# conn_board_v0_1.net
KiCad netlist of a schematic drawn in EAGLE
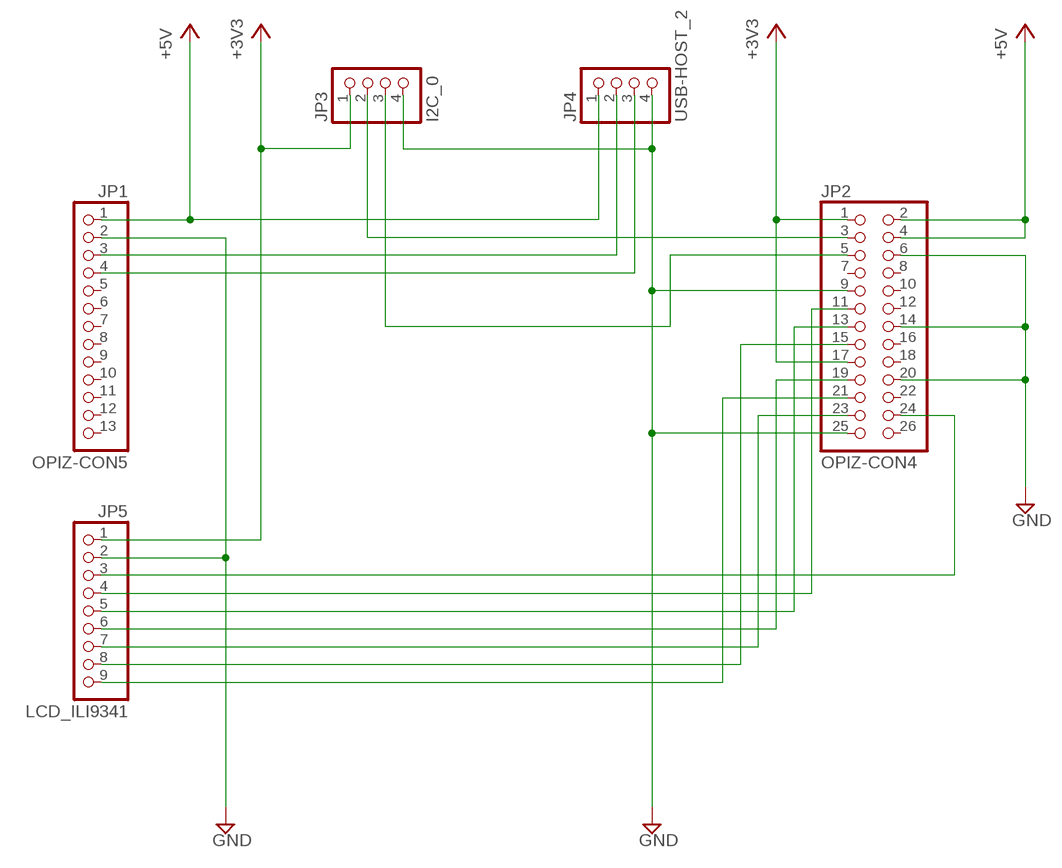
[diagram p0: schematic, sheet 1]

(export (version "E")
  (design (tool "Eeschema 10.0.6"))
  (components
    (comp (ref "JP1")
      (value "OPIZ-CON5")
      (footprint "eagle-import:1X13")
      (libsource (lib "eagle-import") (part "PINHD-1X13"))
    )
    (comp (ref "JP2")
      (value "OPIZ-CON4")
      (footprint "eagle-import:2X13")
      (libsource (lib "eagle-import") (part "PINHD-2X13"))
    )
    (comp (ref "JP3")
      (value "I2C_0")
      (footprint "eagle-import:1X04")
      (libsource (lib "eagle-import") (part "PINHD-1X4"))
    )
    (comp (ref "JP4")
      (value "USB-HOST_2")
      (footprint "eagle-import:1X04")
      (libsource (lib "eagle-import") (part "PINHD-1X4"))
    )
    (comp (ref "JP5")
      (value "LCD_ILI9341")
      (footprint "eagle-import:1X09")
      (libsource (lib "eagle-import") (part "PINHD-1X9"))
    )
  )
  (nets
    (net (code "1") (name "+3V3") (class "Default")
      (node (ref "JP2") (pin "1") (pinfunction "1_1") (pintype "passive"))
      (node (ref "JP2") (pin "17") (pinfunction "17_17") (pintype "passive"))
      (node (ref "JP3") (pin "1") (pinfunction "1_1") (pintype "passive"))
      (node (ref "JP5") (pin "1") (pinfunction "1_1") (pintype "passive"))
    )
    (net (code "2") (name "+5V") (class "Default")
      (node (ref "JP1") (pin "1") (pinfunction "1_1") (pintype "passive"))
      (node (ref "JP2") (pin "2") (pinfunction "2_2") (pintype "passive"))
      (node (ref "JP2") (pin "4") (pinfunction "4_4") (pintype "passive"))
      (node (ref "JP4") (pin "1") (pinfunction "1_1") (pintype "passive"))
    )
    (net (code "3") (name "GND") (class "Default")
      (node (ref "JP1") (pin "2") (pinfunction "2_2") (pintype "passive"))
      (node (ref "JP2") (pin "14") (pinfunction "14_14") (pintype "passive"))
      (node (ref "JP2") (pin "20") (pinfunction "20_20") (pintype "passive"))
      (node (ref "JP2") (pin "25") (pinfunction "25_25") (pintype "passive"))
      (node (ref "JP2") (pin "6") (pinfunction "6_6") (pintype "passive"))
      (node (ref "JP2") (pin "9") (pinfunction "9_9") (pintype "passive"))
      (node (ref "JP3") (pin "4") (pinfunction "4_4") (pintype "passive"))
      (node (ref "JP4") (pin "4") (pinfunction "4_4") (pintype "passive"))
      (node (ref "JP5") (pin "2") (pinfunction "2_2") (pintype "passive"))
    )
    (net (code "4") (name "Net-(JP1-Pad3)") (class "Default")
      (node (ref "JP1") (pin "3") (pinfunction "3_3") (pintype "passive"))
      (node (ref "JP4") (pin "2") (pinfunction "2_2") (pintype "passive"))
    )
    (net (code "5") (name "Net-(JP1-Pad4)") (class "Default")
      (node (ref "JP1") (pin "4") (pinfunction "4_4") (pintype "passive"))
      (node (ref "JP4") (pin "3") (pinfunction "3_3") (pintype "passive"))
    )
    (net (code "6") (name "Net-(JP2-Pad3)") (class "Default")
      (node (ref "JP2") (pin "3") (pinfunction "3_3") (pintype "passive"))
      (node (ref "JP3") (pin "2") (pinfunction "2_2") (pintype "passive"))
    )
    (net (code "7") (name "Net-(JP2-Pad5)") (class "Default")
      (node (ref "JP2") (pin "5") (pinfunction "5_5") (pintype "passive"))
      (node (ref "JP3") (pin "3") (pinfunction "3_3") (pintype "passive"))
    )
    (net (code "8") (name "Net-(JP2-Pad11)") (class "Default")
      (node (ref "JP2") (pin "11") (pinfunction "11_11") (pintype "passive"))
      (node (ref "JP5") (pin "4") (pinfunction "4_4") (pintype "passive"))
    )
    (net (code "9") (name "Net-(JP2-Pad13)") (class "Default")
      (node (ref "JP2") (pin "13") (pinfunction "13_13") (pintype "passive"))
      (node (ref "JP5") (pin "5") (pinfunction "5_5") (pintype "passive"))
    )
    (net (code "10") (name "Net-(JP2-Pad15)") (class "Default")
      (node (ref "JP2") (pin "15") (pinfunction "15_15") (pintype "passive"))
      (node (ref "JP5") (pin "8") (pinfunction "8_8") (pintype "passive"))
    )
    (net (code "11") (name "Net-(JP2-Pad19)") (class "Default")
      (node (ref "JP2") (pin "19") (pinfunction "19_19") (pintype "passive"))
      (node (ref "JP5") (pin "6") (pinfunction "6_6") (pintype "passive"))
    )
    (net (code "12") (name "Net-(JP2-Pad21)") (class "Default")
      (node (ref "JP2") (pin "21") (pinfunction "21_21") (pintype "passive"))
      (node (ref "JP5") (pin "9") (pinfunction "9_9") (pintype "passive"))
    )
    (net (code "13") (name "Net-(JP2-Pad23)") (class "Default")
      (node (ref "JP2") (pin "23") (pinfunction "23_23") (pintype "passive"))
      (node (ref "JP5") (pin "7") (pinfunction "7_7") (pintype "passive"))
    )
    (net (code "14") (name "Net-(JP2-Pad24)") (class "Default")
      (node (ref "JP2") (pin "24") (pinfunction "24_24") (pintype "passive"))
      (node (ref "JP5") (pin "3") (pinfunction "3_3") (pintype "passive"))
    )
    (net (code "15") (name "unconnected-(JP1-Pad5)") (class "Default")
      (node (ref "JP1") (pin "5") (pinfunction "5_5") (pintype "passive"))
    )
    (net (code "16") (name "unconnected-(JP1-Pad6)") (class "Default")
      (node (ref "JP1") (pin "6") (pinfunction "6_6") (pintype "passive"))
    )
    (net (code "17") (name "unconnected-(JP1-Pad7)") (class "Default")
      (node (ref "JP1") (pin "7") (pinfunction "7_7") (pintype "passive"))
    )
    (net (code "18") (name "unconnected-(JP1-Pad8)") (class "Default")
      (node (ref "JP1") (pin "8") (pinfunction "8_8") (pintype "passive"))
    )
    (net (code "19") (name "unconnected-(JP1-Pad9)") (class "Default")
      (node (ref "JP1") (pin "9") (pinfunction "9_9") (pintype "passive"))
    )
    (net (code "20") (name "unconnected-(JP1-Pad10)") (class "Default")
      (node (ref "JP1") (pin "10") (pinfunction "10_10") (pintype "passive"))
    )
    (net (code "21") (name "unconnected-(JP1-Pad11)") (class "Default")
      (node (ref "JP1") (pin "11") (pinfunction "11_11") (pintype "passive"))
    )
    (net (code "22") (name "unconnected-(JP1-Pad12)") (class "Default")
      (node (ref "JP1") (pin "12") (pinfunction "12_12") (pintype "passive"))
    )
    (net (code "23") (name "unconnected-(JP1-Pad13)") (class "Default")
      (node (ref "JP1") (pin "13") (pinfunction "13_13") (pintype "passive"))
    )
    (net (code "24") (name "unconnected-(JP2-Pad7)") (class "Default")
      (node (ref "JP2") (pin "7") (pinfunction "7_7") (pintype "passive"))
    )
    (net (code "25") (name "unconnected-(JP2-Pad8)") (class "Default")
      (node (ref "JP2") (pin "8") (pinfunction "8_8") (pintype "passive"))
    )
    (net (code "26") (name "unconnected-(JP2-Pad10)") (class "Default")
      (node (ref "JP2") (pin "10") (pinfunction "10_10") (pintype "passive"))
    )
    (net (code "27") (name "unconnected-(JP2-Pad12)") (class "Default")
      (node (ref "JP2") (pin "12") (pinfunction "12_12") (pintype "passive"))
    )
    (net (code "28") (name "unconnected-(JP2-Pad16)") (class "Default")
      (node (ref "JP2") (pin "16") (pinfunction "16_16") (pintype "passive"))
    )
    (net (code "29") (name "unconnected-(JP2-Pad18)") (class "Default")
      (node (ref "JP2") (pin "18") (pinfunction "18_18") (pintype "passive"))
    )
    (net (code "30") (name "unconnected-(JP2-Pad22)") (class "Default")
      (node (ref "JP2") (pin "22") (pinfunction "22_22") (pintype "passive"))
    )
    (net (code "31") (name "unconnected-(JP2-Pad26)") (class "Default")
      (node (ref "JP2") (pin "26") (pinfunction "26_26") (pintype "passive"))
    )
  )
)
